# Main.net
KiCad netlist of a schematic drawn in Altium Designer
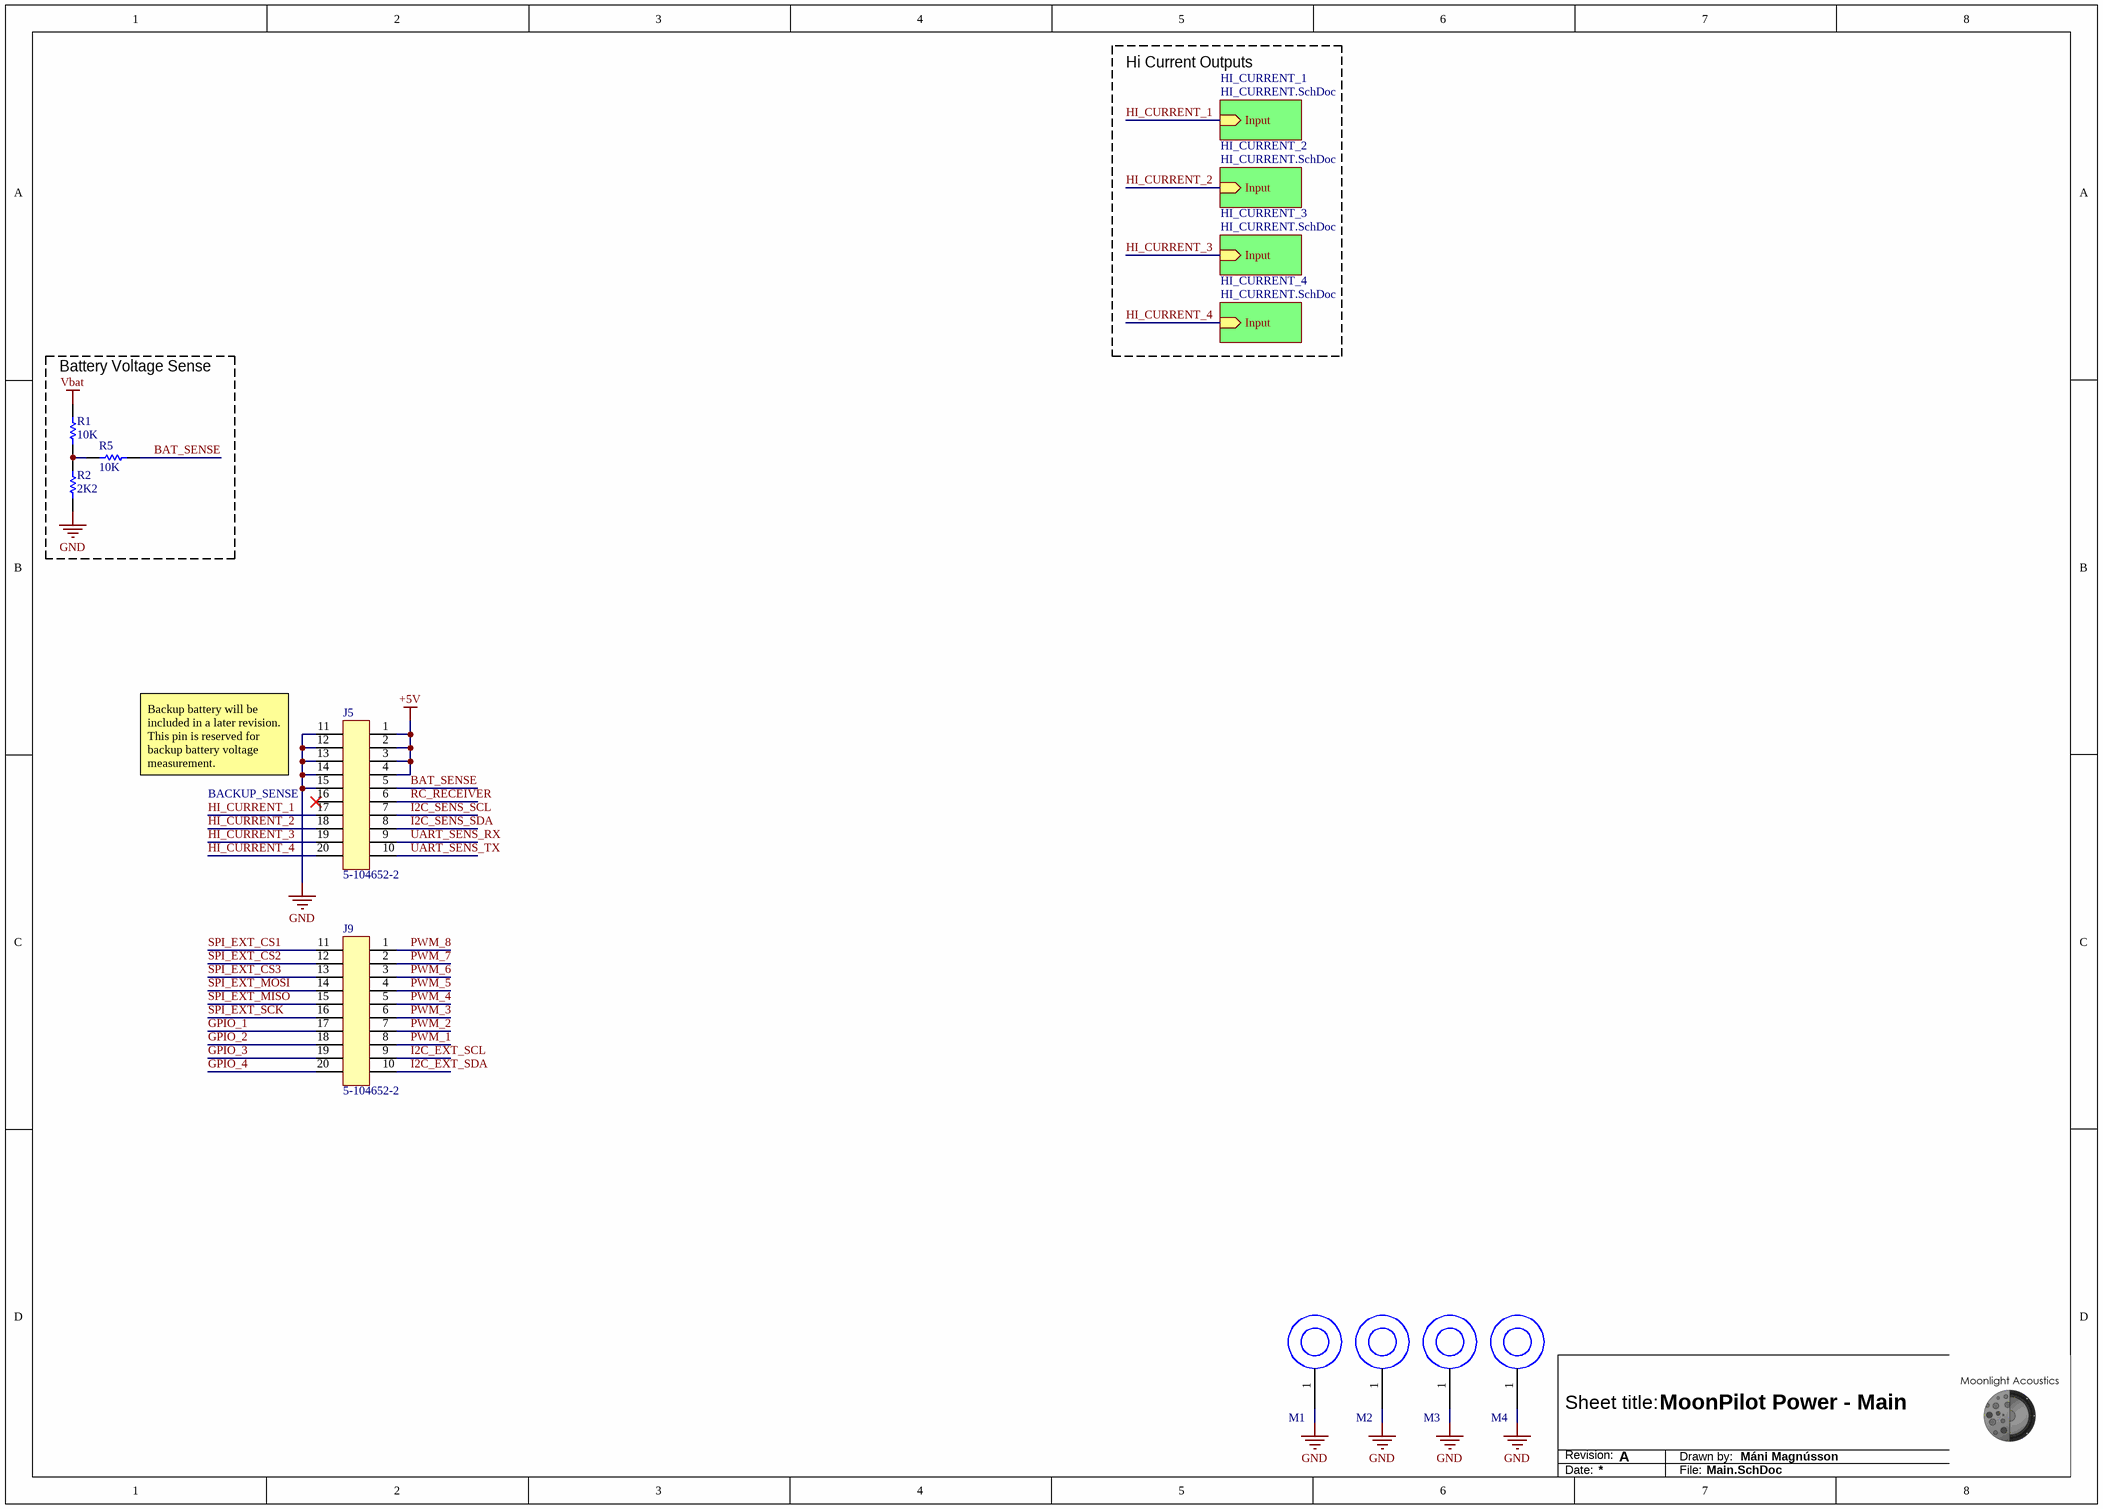
[diagram p0: Main.SchDoc]

(export (version "E")
  (design (tool "Eeschema 10.0.6"))
  (components
    (comp (ref "J5")
      (value "5-104652-2")
      (footprint "5-104652-2")
      (description "Digikey part no. A33547-ND\r\n1.27mm female board to board connector, 2 row")
      (libsource (lib "Moonlight-Components") (part "20 pin vertical board to board female"))
    )
    (comp (ref "J9")
      (value "5-104652-2")
      (footprint "5-104652-2")
      (description "Digikey part no. A33547-ND\r\n1.27mm female board to board connector, 2 row")
      (libsource (lib "Moonlight-Components") (part "20 pin vertical board to board female"))
    )
    (comp (ref "M1")
      (value "Mounting Screw")
      (footprint "M3_SCREW")
      (description "M4 and M3 scew holes, just pick the right footprint")
      (libsource (lib "Moonlight_Components") (part "Mounting Screw"))
    )
    (comp (ref "M2")
      (value "Mounting Screw")
      (footprint "M3_SCREW")
      (description "M4 and M3 scew holes, just pick the right footprint")
      (libsource (lib "Moonlight_Components") (part "Mounting Screw"))
    )
    (comp (ref "M3")
      (value "Mounting Screw")
      (footprint "M3_SCREW")
      (description "M4 and M3 scew holes, just pick the right footprint")
      (libsource (lib "Moonlight_Components") (part "Mounting Screw"))
    )
    (comp (ref "M4")
      (value "Mounting Screw")
      (footprint "M3_SCREW")
      (description "M4 and M3 scew holes, just pick the right footprint")
      (libsource (lib "Moonlight_Components") (part "Mounting Screw"))
    )
    (comp (ref "R1")
      (value "10K")
      (footprint "0805_RES")
      (libsource (lib "Moonlight-Components") (part "Resistor"))
    )
    (comp (ref "R2")
      (value "2K2")
      (footprint "0805_RES")
      (libsource (lib "Moonlight-Components") (part "Resistor"))
    )
    (comp (ref "R5")
      (value "10K")
      (footprint "0603_RES")
      (libsource (lib "Moonlight_Components") (part "Resistor"))
    )
  )
  (nets
    (net (code "1") (name "+5V") (class "Default")
      (node (ref "J5") (pin "1") (pinfunction "*_1") (pintype "passive"))
      (node (ref "J5") (pin "2") (pinfunction "*_2") (pintype "passive"))
      (node (ref "J5") (pin "3") (pinfunction "*_3") (pintype "passive"))
      (node (ref "J5") (pin "4") (pinfunction "*_4") (pintype "passive"))
    )
    (net (code "2") (name "/BAT_SENSE") (class "Default")
      (node (ref "J5") (pin "5") (pinfunction "*_5") (pintype "passive"))
      (node (ref "R5") (pin "2") (pinfunction "2_2") (pintype "passive"))
    )
    (net (code "3") (name "/GPIO_1") (class "Default")
      (node (ref "J9") (pin "17") (pinfunction "*_17") (pintype "passive"))
    )
    (net (code "4") (name "/GPIO_2") (class "Default")
      (node (ref "J9") (pin "18") (pinfunction "*_18") (pintype "passive"))
    )
    (net (code "5") (name "/GPIO_3") (class "Default")
      (node (ref "J9") (pin "19") (pinfunction "*_19") (pintype "passive"))
    )
    (net (code "6") (name "/GPIO_4") (class "Default")
      (node (ref "J9") (pin "20") (pinfunction "*_20") (pintype "passive"))
    )
    (net (code "7") (name "/HI_CURRENT_1") (class "Default")
      (node (ref "J5") (pin "17") (pinfunction "*_17") (pintype "passive"))
    )
    (net (code "8") (name "/HI_CURRENT_2") (class "Default")
      (node (ref "J5") (pin "18") (pinfunction "*_18") (pintype "passive"))
    )
    (net (code "9") (name "/HI_CURRENT_3") (class "Default")
      (node (ref "J5") (pin "19") (pinfunction "*_19") (pintype "passive"))
    )
    (net (code "10") (name "/HI_CURRENT_4") (class "Default")
      (node (ref "J5") (pin "20") (pinfunction "*_20") (pintype "passive"))
    )
    (net (code "11") (name "/I2C_EXT_SCL") (class "Default")
      (node (ref "J9") (pin "9") (pinfunction "*_9") (pintype "passive"))
    )
    (net (code "12") (name "/I2C_EXT_SDA") (class "Default")
      (node (ref "J9") (pin "10") (pinfunction "*_10") (pintype "passive"))
    )
    (net (code "13") (name "/I2C_SENS_SCL") (class "Default")
      (node (ref "J5") (pin "7") (pinfunction "*_7") (pintype "passive"))
    )
    (net (code "14") (name "/I2C_SENS_SDA") (class "Default")
      (node (ref "J5") (pin "8") (pinfunction "*_8") (pintype "passive"))
    )
    (net (code "15") (name "/PWM_1") (class "Default")
      (node (ref "J9") (pin "8") (pinfunction "*_8") (pintype "passive"))
    )
    (net (code "16") (name "/PWM_2") (class "Default")
      (node (ref "J9") (pin "7") (pinfunction "*_7") (pintype "passive"))
    )
    (net (code "17") (name "/PWM_3") (class "Default")
      (node (ref "J9") (pin "6") (pinfunction "*_6") (pintype "passive"))
    )
    (net (code "18") (name "/PWM_4") (class "Default")
      (node (ref "J9") (pin "5") (pinfunction "*_5") (pintype "passive"))
    )
    (net (code "19") (name "/PWM_5") (class "Default")
      (node (ref "J9") (pin "4") (pinfunction "*_4") (pintype "passive"))
    )
    (net (code "20") (name "/PWM_6") (class "Default")
      (node (ref "J9") (pin "3") (pinfunction "*_3") (pintype "passive"))
    )
    (net (code "21") (name "/PWM_7") (class "Default")
      (node (ref "J9") (pin "2") (pinfunction "*_2") (pintype "passive"))
    )
    (net (code "22") (name "/PWM_8") (class "Default")
      (node (ref "J9") (pin "1") (pinfunction "*_1") (pintype "passive"))
    )
    (net (code "23") (name "/RC_RECEIVER") (class "Default")
      (node (ref "J5") (pin "6") (pinfunction "*_6") (pintype "passive"))
    )
    (net (code "24") (name "/SPI_EXT_CS1") (class "Default")
      (node (ref "J9") (pin "11") (pinfunction "*_11") (pintype "passive"))
    )
    (net (code "25") (name "/SPI_EXT_CS2") (class "Default")
      (node (ref "J9") (pin "12") (pinfunction "*_12") (pintype "passive"))
    )
    (net (code "26") (name "/SPI_EXT_CS3") (class "Default")
      (node (ref "J9") (pin "13") (pinfunction "*_13") (pintype "passive"))
    )
    (net (code "27") (name "/SPI_EXT_MISO") (class "Default")
      (node (ref "J9") (pin "15") (pinfunction "*_15") (pintype "passive"))
    )
    (net (code "28") (name "/SPI_EXT_MOSI") (class "Default")
      (node (ref "J9") (pin "14") (pinfunction "*_14") (pintype "passive"))
    )
    (net (code "29") (name "/SPI_EXT_SCK") (class "Default")
      (node (ref "J9") (pin "16") (pinfunction "*_16") (pintype "passive"))
    )
    (net (code "30") (name "/UART_SENS_RX") (class "Default")
      (node (ref "J5") (pin "9") (pinfunction "*_9") (pintype "passive"))
    )
    (net (code "31") (name "/UART_SENS_TX") (class "Default")
      (node (ref "J5") (pin "10") (pinfunction "*_10") (pintype "passive"))
    )
    (net (code "32") (name "GND") (class "Default")
      (node (ref "J5") (pin "11") (pinfunction "*_11") (pintype "passive"))
      (node (ref "J5") (pin "12") (pinfunction "*_12") (pintype "passive"))
      (node (ref "J5") (pin "13") (pinfunction "*_13") (pintype "passive"))
      (node (ref "J5") (pin "14") (pinfunction "*_14") (pintype "passive"))
      (node (ref "J5") (pin "15") (pinfunction "*_15") (pintype "passive"))
      (node (ref "M1") (pin "1") (pinfunction "19_1") (pintype "passive"))
      (node (ref "M2") (pin "1") (pinfunction "19_1") (pintype "passive"))
      (node (ref "M3") (pin "1") (pinfunction "19_1") (pintype "passive"))
      (node (ref "M4") (pin "1") (pinfunction "19_1") (pintype "passive"))
      (node (ref "R2") (pin "2") (pinfunction "2_2") (pintype "passive"))
    )
    (net (code "33") (name "Net-(R1-Pad2)") (class "Default")
      (node (ref "R1") (pin "2") (pinfunction "2_2") (pintype "passive"))
      (node (ref "R2") (pin "1") (pinfunction "1_1") (pintype "passive"))
      (node (ref "R5") (pin "1") (pinfunction "1_1") (pintype "passive"))
    )
    (net (code "34") (name "Vbat") (class "Default")
      (node (ref "R1") (pin "1") (pinfunction "1_1") (pintype "passive"))
    )
    (net (code "35") (name "unconnected-(J5-*-Pad16)") (class "Default")
      (node (ref "J5") (pin "16") (pinfunction "*_16") (pintype "passive+no_connect"))
    )
  )
)
